# LMS.net
KiCad netlist of a schematic drawn in Altium Designer
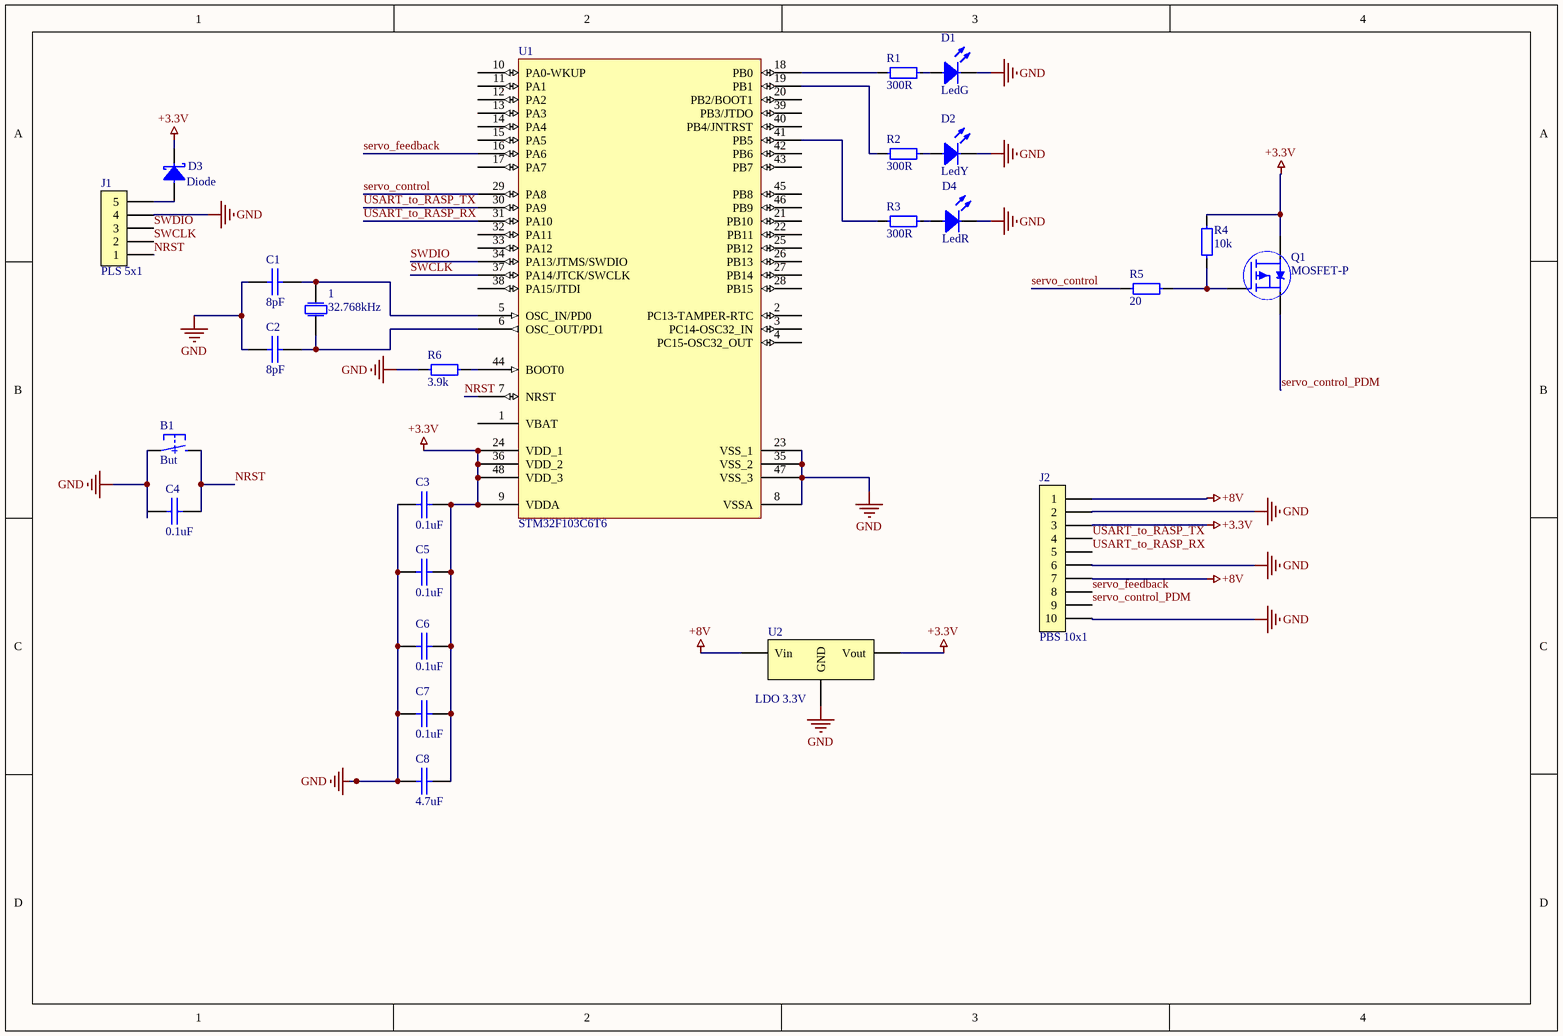
[diagram p0: LMS.SchDoc]

(export (version "E")
  (design (tool "Eeschema 10.0.6"))
  (components
    (comp (ref "1")
      (value "32.768kHz")
      (footprint "Crystal ABM")
      (description "32.768kHz, SMD, 6 pF")
      (fields (field (name "MANUFACTURER") "Seiko") (field (name "PART NUMBER") "9000417960"))
      (libsource (lib "BRT_Components") (part "Crystal 32.768kHz"))
    )
    (comp (ref "B1")
      (value "But")
      (footprint "BUTTON 6x3.5")
      (description "Button 2 Conn SMD")
      (fields
        (field (name "PART NUMBER") "L-KLS7-TS3608-5.0-180")
        (field (name "MANUFACTURER") "KLS electronic co ltd")
      )
      (libsource (lib "BRT_Components") (part "Button 2 Conn"))
    )
    (comp (ref "C1")
      (value "8pF")
      (footprint "0805 Capicator")
      (description "8pF NPO 50V, 5%, 0805")
      (fields
        (field (name "MANUFACTURER") "Murata Manufacturing")
        (field (name "PART NUMBER") "MLCC8.0pFNPO50V5%0805")
      )
      (libsource (lib "BRT_Components") (part "Cap 8pF (0805)_1"))
    )
    (comp (ref "C2")
      (value "8pF")
      (footprint "0805 Capicator")
      (description "8pF NPO 50V, 5%, 0805")
      (fields
        (field (name "MANUFACTURER") "Murata Manufacturing")
        (field (name "PART NUMBER") "MLCC8.0pFNPO50V5%0805")
      )
      (libsource (lib "BRT_Components") (part "Cap 8pF (0805)_1"))
    )
    (comp (ref "C3")
      (value "0.1uF")
      (footprint "0805 Capicator")
      (description "0.1uF X7R 25V 10% 0805")
      (fields
        (field (name "MANUFACTURER") "Murata Manufacturing")
        (field (name "PART NUMBER") "GRM21BR71E104KA01L")
      )
      (libsource (lib "BRT_Components") (part "Cap 0.1uF (0805)"))
    )
    (comp (ref "C4")
      (value "0.1uF")
      (footprint "0805 Capicator")
      (description "0.1uF X7R 25V 10% 0805")
      (fields
        (field (name "MANUFACTURER") "Murata Manufacturing")
        (field (name "PART NUMBER") "GRM21BR71E104KA01L")
      )
      (libsource (lib "BRT_Components") (part "Cap 0.1uF (0805)"))
    )
    (comp (ref "C5")
      (value "0.1uF")
      (footprint "0805 Capicator")
      (description "0.1uF X7R 25V 10% 0805")
      (fields
        (field (name "MANUFACTURER") "Murata Manufacturing")
        (field (name "PART NUMBER") "GRM21BR71E104KA01L")
      )
      (libsource (lib "BRT_Components") (part "Cap 0.1uF (0805)"))
    )
    (comp (ref "C6")
      (value "0.1uF")
      (footprint "0805 Capicator")
      (description "0.1uF X7R 25V 10% 0805")
      (fields
        (field (name "MANUFACTURER") "Murata Manufacturing")
        (field (name "PART NUMBER") "GRM21BR71E104KA01L")
      )
      (libsource (lib "BRT_Components") (part "Cap 0.1uF (0805)"))
    )
    (comp (ref "C7")
      (value "0.1uF")
      (footprint "0805 Capicator")
      (description "0.1uF X7R 25V 10% 0805")
      (fields
        (field (name "MANUFACTURER") "Murata Manufacturing")
        (field (name "PART NUMBER") "GRM21BR71E104KA01L")
      )
      (libsource (lib "BRT_Components") (part "Cap 0.1uF (0805)"))
    )
    (comp (ref "C8")
      (value "4.7uF")
      (footprint "0805 Capicator")
      (description "4.7uF X5R 10% 25V 0805")
      (fields
        (field (name "MANUFACTURER") "Murata Manufacturing")
        (field (name "PART NUMBER") "GRM21BR61E475KA12L")
      )
      (libsource (lib "BRT_Components") (part "Cap 4.7uF (0805)"))
    )
    (comp (ref "D1")
      (value "LedG")
      (footprint "0805 LED")
      (description "Led Green SMD 1608, 120°, 525nM")
      (fields
        (field (name "PART NUMBER") "TO-1608BC-PG")
        (field (name "MANUFACTURER") "Taiwan Oasis Technology")
      )
      (libsource (lib "BRT_Components") (part "Led Green"))
    )
    (comp (ref "D2")
      (value "LedY")
      (footprint "0805 LED")
      (description "SMD 1608, 247mcd, 120°, 592nM (High Bright Yellow)")
      (fields
        (field (name "PART NUMBER") "TO-1608BC-MYF")
        (field (name "MANUFACTURER") "Taiwan Oasis Technology")
      )
      (libsource (lib "BRT_Components") (part "Led Yellow"))
    )
    (comp (ref "D3")
      (value "Diode")
      (footprint "SMA")
      (description "Diode Schottky 3A 40V")
      (fields (field (name "PART NUMBER") "B340A-E3/61T") (field (name "MANUFACTURER") "Vishay"))
      (libsource (lib "BRT_Components") (part "Diode Schottky (SMA)"))
    )
    (comp (ref "D4")
      (value "LedR")
      (footprint "0805 LED")
      (description "SMD 1608, 112mcd, 120°, 630nM (Ultra Bright Red)")
      (fields
        (field (name "PART NUMBER") "TO-1608BC-MRE")
        (field (name "MANUFACTURER") "Taiwan Oasis Technology")
      )
      (libsource (lib "BRT_Components") (part "Led Red"))
    )
    (comp (ref "J1")
      (value "PLS 5x1")
      (footprint "PLS 5x1")
      (description "Header, 5-Pin")
      (libsource (lib "BRT_Components") (part "Conn 5 (PLS)"))
    )
    (comp (ref "J2")
      (value "PBS 10x1")
      (footprint "PBS10")
      (description "Female")
      (fields
        (field (name "PART NUMBER") "DS1023-1*10S21")
        (field (name "MANUFACTURER") "Ningbo connfly electronic")
      )
      (libsource (lib "BRT_Components") (part "Conn 10 (PBS)"))
    )
    (comp (ref "Q1")
      (value "MOSFET-P")
      (footprint "SOT-23")
      (description "P-Channel Power MOSFET 12V to 20V, Infineon")
      (fields
        (field (name "PART NUMBER") "IRLML2246TRPBF")
        (field (name "MANUFACTURER") "Infineon Technologies")
      )
      (libsource (lib "BRT_Components") (part "MOSFET-P [IRLML]"))
    )
    (comp (ref "R1")
      (value "300R")
      (footprint "0805 Resistor")
      (description "0.125W 0805 300R, 1%")
      (fields (field (name "PART NUMBER") "RC0805FR-07300RL") (field (name "MANUFACTURER") "Taiwan"))
      (libsource (lib "BRT_Components") (part "Res 300R (0805)"))
    )
    (comp (ref "R2")
      (value "300R")
      (footprint "0805 Resistor")
      (description "0.125W 0805 300R, 1%")
      (fields (field (name "PART NUMBER") "RC0805FR-07300RL") (field (name "MANUFACTURER") "Taiwan"))
      (libsource (lib "BRT_Components") (part "Res 300R (0805)"))
    )
    (comp (ref "R3")
      (value "300R")
      (footprint "0805 Resistor")
      (description "0.125W 0805 300R, 1%")
      (fields (field (name "PART NUMBER") "RC0805FR-07300RL") (field (name "MANUFACTURER") "Taiwan"))
      (libsource (lib "BRT_Components") (part "Res 300R (0805)"))
    )
    (comp (ref "R4")
      (value "10k")
      (footprint "0805 Resistor")
      (description "0.125W 0805 10k, 1%")
      (fields (field (name "PART NUMBER") "RC0805FR-0710KL") (field (name "MANUFACTURER") "Taiwan"))
      (libsource (lib "BRT_Components") (part "Res 10k (0805)"))
    )
    (comp (ref "R5")
      (value "20")
      (footprint "0805 Resistor")
      (description "0.125W 0805 10k, 1%")
      (fields (field (name "PART NUMBER") "RC0805FR-0710KL") (field (name "MANUFACTURER") "Taiwan"))
      (libsource (lib "BRT_Components") (part "Res 10k (0805)"))
    )
    (comp (ref "R6")
      (value "3.9k")
      (footprint "0805 Resistor")
      (description "0.125W 0805 1k, 1%")
      (fields (field (name "PART NUMBER") "RC0805FR-071KL") (field (name "MANUFACTURER") "Taiwan"))
      (libsource (lib "BRT_Components") (part "Res 1k (0805)"))
    )
    (comp (ref "U1")
      (value "STM32F103C6T6")
      (footprint "BRT_Components:LQFP48")
      (description "STM32 ARM-based 32-bit MCU with 32 Kbytes Flash, 48-pin LQFP, Industrial Temperature")
      (fields (field (name "PUBLISHER") "Altium Limited"))
      (libsource (lib "ST Microcontroller 32-Bit STM32") (part "STM32F103C6T6"))
    )
    (comp (ref "U2")
      (value "LDO 3.3V")
      (footprint "SOT-223")
      (description "LDO Regulator Pos 3.3V 1.3A 4-Pin(3+Tab) SOT-223 T/R")
      (fields (field (name "PART NUMBER") "LD1117S33CTR") (field (name "MANUFACTURER") "STMicroelectronics"))
      (libsource (lib "BRT_Components") (part "LDO 3.3V [LD]"))
    )
  )
  (nets
    (net (code "1") (name "+3.3V") (class "Default")
      (node (ref "C3") (pin "1") (pinfunction "1_1") (pintype "passive"))
      (node (ref "C5") (pin "1") (pinfunction "1_1") (pintype "passive"))
      (node (ref "C6") (pin "1") (pinfunction "1_1") (pintype "passive"))
      (node (ref "C7") (pin "1") (pinfunction "1_1") (pintype "passive"))
      (node (ref "C8") (pin "1") (pinfunction "1_1") (pintype "passive"))
      (node (ref "D3") (pin "2") (pinfunction "2_2") (pintype "passive"))
      (node (ref "J2") (pin "3") (pinfunction "3_3") (pintype "passive"))
      (node (ref "Q1") (pin "3") (pinfunction "Drain_3") (pintype "passive"))
      (node (ref "R4") (pin "2") (pinfunction "2_2") (pintype "passive"))
      (node (ref "U1") (pin "24") (pinfunction "VDD_1_24") (pintype "power_in"))
      (node (ref "U1") (pin "36") (pinfunction "VDD_2_36") (pintype "power_in"))
      (node (ref "U1") (pin "48") (pinfunction "VDD_3_48") (pintype "power_in"))
      (node (ref "U1") (pin "9") (pinfunction "VDDA_9") (pintype "power_in"))
      (node (ref "U2") (pin "2") (pinfunction "Vout_2") (pintype "power_in"))
    )
    (net (code "2") (name "+8V") (class "Default")
      (node (ref "J2") (pin "1") (pinfunction "1_1") (pintype "passive"))
      (node (ref "J2") (pin "7") (pinfunction "7_7") (pintype "passive"))
      (node (ref "U2") (pin "3") (pinfunction "Vin_3") (pintype "power_in"))
    )
    (net (code "3") (name "/NRST") (class "Default")
      (node (ref "B1") (pin "2") (pinfunction "2_2") (pintype "passive"))
      (node (ref "C4") (pin "2") (pinfunction "2_2") (pintype "passive"))
      (node (ref "J1") (pin "1") (pinfunction "1_1") (pintype "passive"))
      (node (ref "U1") (pin "7") (pinfunction "NRST_7") (pintype "bidirectional"))
    )
    (net (code "4") (name "/SWCLK") (class "Default")
      (node (ref "J1") (pin "2") (pinfunction "2_2") (pintype "passive"))
      (node (ref "U1") (pin "37") (pinfunction "PA14/JTCK/SWCLK_37") (pintype "bidirectional"))
    )
    (net (code "5") (name "/SWDIO") (class "Default")
      (node (ref "J1") (pin "3") (pinfunction "3_3") (pintype "passive"))
      (node (ref "U1") (pin "34") (pinfunction "PA13/JTMS/SWDIO_34") (pintype "bidirectional"))
    )
    (net (code "6") (name "/USART_to_RASP_RX") (class "Default")
      (node (ref "J2") (pin "5") (pinfunction "5_5") (pintype "passive"))
      (node (ref "U1") (pin "31") (pinfunction "PA10_31") (pintype "bidirectional"))
    )
    (net (code "7") (name "/USART_to_RASP_TX") (class "Default")
      (node (ref "J2") (pin "4") (pinfunction "4_4") (pintype "passive"))
      (node (ref "U1") (pin "30") (pinfunction "PA9_30") (pintype "bidirectional"))
    )
    (net (code "8") (name "/servo_control") (class "Default")
      (node (ref "R5") (pin "1") (pinfunction "1_1") (pintype "passive"))
      (node (ref "U1") (pin "29") (pinfunction "PA8_29") (pintype "bidirectional"))
    )
    (net (code "9") (name "/servo_control_PDM") (class "Default")
      (node (ref "J2") (pin "9") (pinfunction "9_9") (pintype "passive"))
      (node (ref "Q1") (pin "2") (pinfunction "Source_2") (pintype "passive"))
    )
    (net (code "10") (name "/servo_feedback") (class "Default")
      (node (ref "J2") (pin "8") (pinfunction "8_8") (pintype "passive"))
      (node (ref "U1") (pin "16") (pinfunction "PA6_16") (pintype "bidirectional"))
    )
    (net (code "11") (name "GND") (class "Default")
      (node (ref "B1") (pin "1") (pinfunction "1_1") (pintype "passive"))
      (node (ref "C1") (pin "1") (pinfunction "1_1") (pintype "passive"))
      (node (ref "C2") (pin "1") (pinfunction "1_1") (pintype "passive"))
      (node (ref "C3") (pin "2") (pinfunction "2_2") (pintype "passive"))
      (node (ref "C5") (pin "2") (pinfunction "2_2") (pintype "passive"))
      (node (ref "C6") (pin "2") (pinfunction "2_2") (pintype "passive"))
      (node (ref "C7") (pin "2") (pinfunction "2_2") (pintype "passive"))
      (node (ref "C8") (pin "2") (pinfunction "2_2") (pintype "passive"))
      (node (ref "D1") (pin "2") (pinfunction "2_2") (pintype "passive"))
      (node (ref "D2") (pin "2") (pinfunction "2_2") (pintype "passive"))
      (node (ref "D4") (pin "2") (pinfunction "2_2") (pintype "passive"))
      (node (ref "J1") (pin "4") (pinfunction "4_4") (pintype "passive"))
      (node (ref "J2") (pin "10") (pinfunction "10_10") (pintype "passive"))
      (node (ref "J2") (pin "2") (pinfunction "2_2") (pintype "passive"))
      (node (ref "J2") (pin "6") (pinfunction "6_6") (pintype "passive"))
      (node (ref "R6") (pin "1") (pinfunction "1_1") (pintype "passive"))
      (node (ref "U1") (pin "23") (pinfunction "VSS_1_23") (pintype "power_in"))
      (node (ref "U1") (pin "35") (pinfunction "VSS_2_35") (pintype "power_in"))
      (node (ref "U1") (pin "47") (pinfunction "VSS_3_47") (pintype "power_in"))
      (node (ref "U1") (pin "8") (pinfunction "VSSA_8") (pintype "power_in"))
      (node (ref "U2") (pin "1") (pinfunction "GND_1") (pintype "power_in"))
    )
    (net (code "12") (name "Net-(D1-Pad1)") (class "Default")
      (node (ref "D1") (pin "1") (pinfunction "1_1") (pintype "passive"))
      (node (ref "R1") (pin "2") (pinfunction "2_2") (pintype "passive"))
    )
    (net (code "13") (name "Net-(D2-Pad1)") (class "Default")
      (node (ref "D2") (pin "1") (pinfunction "1_1") (pintype "passive"))
      (node (ref "R2") (pin "2") (pinfunction "2_2") (pintype "passive"))
    )
    (net (code "14") (name "Net-(D3-Pad1)") (class "Default")
      (node (ref "D3") (pin "1") (pinfunction "1_1") (pintype "passive"))
      (node (ref "J1") (pin "5") (pinfunction "5_5") (pintype "passive"))
    )
    (net (code "15") (name "Net-(D4-Pad1)") (class "Default")
      (node (ref "D4") (pin "1") (pinfunction "1_1") (pintype "passive"))
      (node (ref "R3") (pin "2") (pinfunction "2_2") (pintype "passive"))
    )
    (net (code "16") (name "Net-(Q1-Gate)") (class "Default")
      (node (ref "Q1") (pin "1") (pinfunction "Gate_1") (pintype "passive"))
      (node (ref "R4") (pin "1") (pinfunction "1_1") (pintype "passive"))
      (node (ref "R5") (pin "2") (pinfunction "2_2") (pintype "passive"))
    )
    (net (code "17") (name "Net-(U1-BOOT0)") (class "Default")
      (node (ref "R6") (pin "2") (pinfunction "2_2") (pintype "passive"))
      (node (ref "U1") (pin "44") (pinfunction "BOOT0_44") (pintype "input"))
    )
    (net (code "18") (name "Net-(U1-OSC_IN{slash}PD0)") (class "Default")
      (node (ref "1") (pin "2") (pinfunction "2_2") (pintype "passive"))
      (node (ref "C1") (pin "2") (pinfunction "2_2") (pintype "passive"))
      (node (ref "U1") (pin "5") (pinfunction "OSC_IN/PD0_5") (pintype "input"))
    )
    (net (code "19") (name "Net-(U1-OSC_OUT{slash}PD1)") (class "Default")
      (node (ref "1") (pin "1") (pinfunction "1_1") (pintype "passive"))
      (node (ref "C2") (pin "2") (pinfunction "2_2") (pintype "passive"))
      (node (ref "U1") (pin "6") (pinfunction "OSC_OUT/PD1_6") (pintype "output"))
    )
    (net (code "20") (name "Net-(U1-PB0)") (class "Default")
      (node (ref "R1") (pin "1") (pinfunction "1_1") (pintype "passive"))
      (node (ref "U1") (pin "18") (pinfunction "PB0_18") (pintype "bidirectional"))
    )
    (net (code "21") (name "Net-(U1-PB1)") (class "Default")
      (node (ref "R2") (pin "1") (pinfunction "1_1") (pintype "passive"))
      (node (ref "U1") (pin "19") (pinfunction "PB1_19") (pintype "bidirectional"))
    )
    (net (code "22") (name "Net-(U1-PB5)") (class "Default")
      (node (ref "R3") (pin "1") (pinfunction "1_1") (pintype "passive"))
      (node (ref "U1") (pin "41") (pinfunction "PB5_41") (pintype "bidirectional"))
    )
    (net (code "23") (name "unconnected-(C4-Pad1)") (class "Default")
      (node (ref "C4") (pin "1") (pinfunction "1_1") (pintype "passive"))
    )
    (net (code "24") (name "unconnected-(U1-PA0-WKUP-Pad10)") (class "Default")
      (node (ref "U1") (pin "10") (pinfunction "PA0-WKUP_10") (pintype "bidirectional"))
    )
    (net (code "25") (name "unconnected-(U1-PA1-Pad11)") (class "Default")
      (node (ref "U1") (pin "11") (pinfunction "PA1_11") (pintype "bidirectional"))
    )
    (net (code "26") (name "unconnected-(U1-PA2-Pad12)") (class "Default")
      (node (ref "U1") (pin "12") (pinfunction "PA2_12") (pintype "bidirectional"))
    )
    (net (code "27") (name "unconnected-(U1-PA3-Pad13)") (class "Default")
      (node (ref "U1") (pin "13") (pinfunction "PA3_13") (pintype "bidirectional"))
    )
    (net (code "28") (name "unconnected-(U1-PA4-Pad14)") (class "Default")
      (node (ref "U1") (pin "14") (pinfunction "PA4_14") (pintype "bidirectional"))
    )
    (net (code "29") (name "unconnected-(U1-PA5-Pad15)") (class "Default")
      (node (ref "U1") (pin "15") (pinfunction "PA5_15") (pintype "bidirectional"))
    )
    (net (code "30") (name "unconnected-(U1-PA7-Pad17)") (class "Default")
      (node (ref "U1") (pin "17") (pinfunction "PA7_17") (pintype "bidirectional"))
    )
    (net (code "31") (name "unconnected-(U1-PA11-Pad32)") (class "Default")
      (node (ref "U1") (pin "32") (pinfunction "PA11_32") (pintype "bidirectional"))
    )
    (net (code "32") (name "unconnected-(U1-PA12-Pad33)") (class "Default")
      (node (ref "U1") (pin "33") (pinfunction "PA12_33") (pintype "bidirectional"))
    )
    (net (code "33") (name "unconnected-(U1-PA15{slash}JTDI-Pad38)") (class "Default")
      (node (ref "U1") (pin "38") (pinfunction "PA15/JTDI_38") (pintype "bidirectional"))
    )
    (net (code "34") (name "unconnected-(U1-PB2{slash}BOOT1-Pad20)") (class "Default")
      (node (ref "U1") (pin "20") (pinfunction "PB2/BOOT1_20") (pintype "bidirectional"))
    )
    (net (code "35") (name "unconnected-(U1-PB3{slash}JTDO-Pad39)") (class "Default")
      (node (ref "U1") (pin "39") (pinfunction "PB3/JTDO_39") (pintype "bidirectional"))
    )
    (net (code "36") (name "unconnected-(U1-PB4{slash}JNTRST-Pad40)") (class "Default")
      (node (ref "U1") (pin "40") (pinfunction "PB4/JNTRST_40") (pintype "bidirectional"))
    )
    (net (code "37") (name "unconnected-(U1-PB6-Pad42)") (class "Default")
      (node (ref "U1") (pin "42") (pinfunction "PB6_42") (pintype "bidirectional"))
    )
    (net (code "38") (name "unconnected-(U1-PB7-Pad43)") (class "Default")
      (node (ref "U1") (pin "43") (pinfunction "PB7_43") (pintype "bidirectional"))
    )
    (net (code "39") (name "unconnected-(U1-PB8-Pad45)") (class "Default")
      (node (ref "U1") (pin "45") (pinfunction "PB8_45") (pintype "bidirectional"))
    )
    (net (code "40") (name "unconnected-(U1-PB9-Pad46)") (class "Default")
      (node (ref "U1") (pin "46") (pinfunction "PB9_46") (pintype "bidirectional"))
    )
    (net (code "41") (name "unconnected-(U1-PB10-Pad21)") (class "Default")
      (node (ref "U1") (pin "21") (pinfunction "PB10_21") (pintype "bidirectional"))
    )
    (net (code "42") (name "unconnected-(U1-PB11-Pad22)") (class "Default")
      (node (ref "U1") (pin "22") (pinfunction "PB11_22") (pintype "bidirectional"))
    )
    (net (code "43") (name "unconnected-(U1-PB12-Pad25)") (class "Default")
      (node (ref "U1") (pin "25") (pinfunction "PB12_25") (pintype "bidirectional"))
    )
    (net (code "44") (name "unconnected-(U1-PB13-Pad26)") (class "Default")
      (node (ref "U1") (pin "26") (pinfunction "PB13_26") (pintype "bidirectional"))
    )
    (net (code "45") (name "unconnected-(U1-PB14-Pad27)") (class "Default")
      (node (ref "U1") (pin "27") (pinfunction "PB14_27") (pintype "bidirectional"))
    )
    (net (code "46") (name "unconnected-(U1-PB15-Pad28)") (class "Default")
      (node (ref "U1") (pin "28") (pinfunction "PB15_28") (pintype "bidirectional"))
    )
    (net (code "47") (name "unconnected-(U1-PC13-TAMPER-RTC-Pad2)") (class "Default")
      (node (ref "U1") (pin "2") (pinfunction "PC13-TAMPER-RTC_2") (pintype "bidirectional"))
    )
    (net (code "48") (name "unconnected-(U1-PC14-OSC32_IN-Pad3)") (class "Default")
      (node (ref "U1") (pin "3") (pinfunction "PC14-OSC32_IN_3") (pintype "bidirectional"))
    )
    (net (code "49") (name "unconnected-(U1-PC15-OSC32_OUT-Pad4)") (class "Default")
      (node (ref "U1") (pin "4") (pinfunction "PC15-OSC32_OUT_4") (pintype "bidirectional"))
    )
    (net (code "50") (name "unconnected-(U1-VBAT-Pad1)") (class "Default")
      (node (ref "U1") (pin "1") (pinfunction "VBAT_1") (pintype "power_in"))
    )
  )
)
